# main.net
KiCad netlist of a schematic drawn in EAGLE
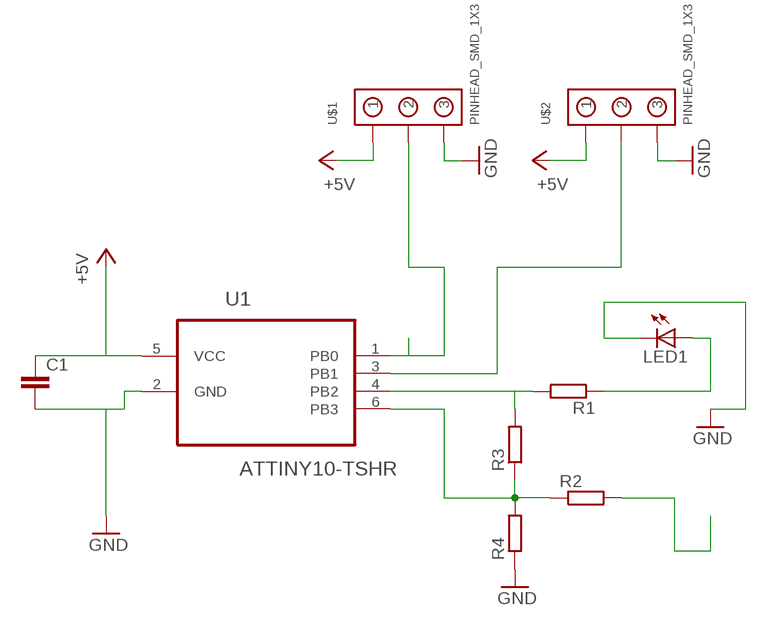
[diagram p0: schematic, sheet 1]

(export (version "E")
  (design (tool "Eeschema 10.0.6"))
  (components
    (comp (ref "C1")
      (value "C-EUC0805K")
      (footprint "eagle-import:C0805K")
      (libsource (lib "eagle-import") (part "C-EUC0805K"))
    )
    (comp (ref "LED1")
      (value "LED_LEDP-LCC-2-BACK")
      (footprint "eagle-import:LED_HOLE_4MM")
      (libsource (lib "eagle-import") (part "LED_LEDP-LCC-2-BACK"))
    )
    (comp (ref "R1")
      (value "R-EU_R0603")
      (footprint "eagle-import:R0603")
      (libsource (lib "eagle-import") (part "R-EU_R0603"))
    )
    (comp (ref "R2")
      (value "R-EU_R0603")
      (footprint "eagle-import:R0603")
      (libsource (lib "eagle-import") (part "R-EU_R0603"))
    )
    (comp (ref "R3")
      (value "R-EU_R0603")
      (footprint "eagle-import:R0603")
      (libsource (lib "eagle-import") (part "R-EU_R0603"))
    )
    (comp (ref "R4")
      (value "R-EU_R0603")
      (footprint "eagle-import:R0603")
      (libsource (lib "eagle-import") (part "R-EU_R0603"))
    )
    (comp (ref "U$1")
      (value "PINHEAD_SMD_1X3")
      (footprint "eagle-import:PINHEAD_1X3")
      (libsource (lib "eagle-import") (part "PINHEAD_SMD_1X3"))
    )
    (comp (ref "U$2")
      (value "PINHEAD_SMD_1X3")
      (footprint "eagle-import:PINHEAD_1X3")
      (libsource (lib "eagle-import") (part "PINHEAD_SMD_1X3"))
    )
    (comp (ref "U1")
      (value "ATTINY10-TSHR")
      (footprint "eagle-import:SOT95P280X145-6N")
      (libsource (lib "eagle-import") (part "ATTINY10-TSHR"))
    )
  )
  (nets
    (net (code "1") (name "+5V") (class "Default")
      (node (ref "C1") (pin "1") (pinfunction "1_1") (pintype "passive"))
      (node (ref "U$1") (pin "P$1") (pinfunction "1_P$1") (pintype "bidirectional"))
      (node (ref "U$2") (pin "P$1") (pinfunction "1_P$1") (pintype "bidirectional"))
      (node (ref "U1") (pin "5") (pinfunction "VCC_5") (pintype "power_in"))
    )
    (net (code "2") (name "GND") (class "Default")
      (node (ref "C1") (pin "2") (pinfunction "2_2") (pintype "passive"))
      (node (ref "LED1") (pin "C") (pinfunction "C_C") (pintype "passive"))
      (node (ref "R4") (pin "1") (pinfunction "1_1") (pintype "passive"))
      (node (ref "U$1") (pin "P$3") (pinfunction "3_P$3") (pintype "bidirectional"))
      (node (ref "U$2") (pin "P$3") (pinfunction "3_P$3") (pintype "bidirectional"))
      (node (ref "U1") (pin "2") (pinfunction "GND_2") (pintype "passive"))
    )
    (net (code "3") (name "Net-(LED1-PadA)") (class "Default")
      (node (ref "LED1") (pin "A") (pinfunction "A_A") (pintype "passive"))
      (node (ref "R1") (pin "1") (pinfunction "1_1") (pintype "passive"))
    )
    (net (code "4") (name "Net-(U$1-2)") (class "Default")
      (node (ref "U$1") (pin "P$2") (pinfunction "2_P$2") (pintype "bidirectional"))
      (node (ref "U1") (pin "1") (pinfunction "PB0_1") (pintype "bidirectional"))
    )
    (net (code "5") (name "Net-(U$2-2)") (class "Default")
      (node (ref "U$2") (pin "P$2") (pinfunction "2_P$2") (pintype "bidirectional"))
      (node (ref "U1") (pin "3") (pinfunction "PB1_3") (pintype "bidirectional"))
    )
    (net (code "6") (name "Net-(U1-PB2)") (class "Default")
      (node (ref "R1") (pin "2") (pinfunction "2_2") (pintype "passive"))
      (node (ref "R3") (pin "2") (pinfunction "2_2") (pintype "passive"))
      (node (ref "U1") (pin "4") (pinfunction "PB2_4") (pintype "bidirectional"))
    )
    (net (code "7") (name "Net-(U1-PB3)") (class "Default")
      (node (ref "R2") (pin "1") (pinfunction "1_1") (pintype "passive"))
      (node (ref "R3") (pin "1") (pinfunction "1_1") (pintype "passive"))
      (node (ref "R4") (pin "2") (pinfunction "2_2") (pintype "passive"))
      (node (ref "U1") (pin "6") (pinfunction "PB3_6") (pintype "bidirectional"))
    )
    (net (code "8") (name "unconnected-(R2-Pad2)") (class "Default")
      (node (ref "R2") (pin "2") (pinfunction "2_2") (pintype "passive"))
    )
  )
)
